# EL-100-020-010-AnalogIN.net
KiCad netlist of a schematic drawn in EAGLE
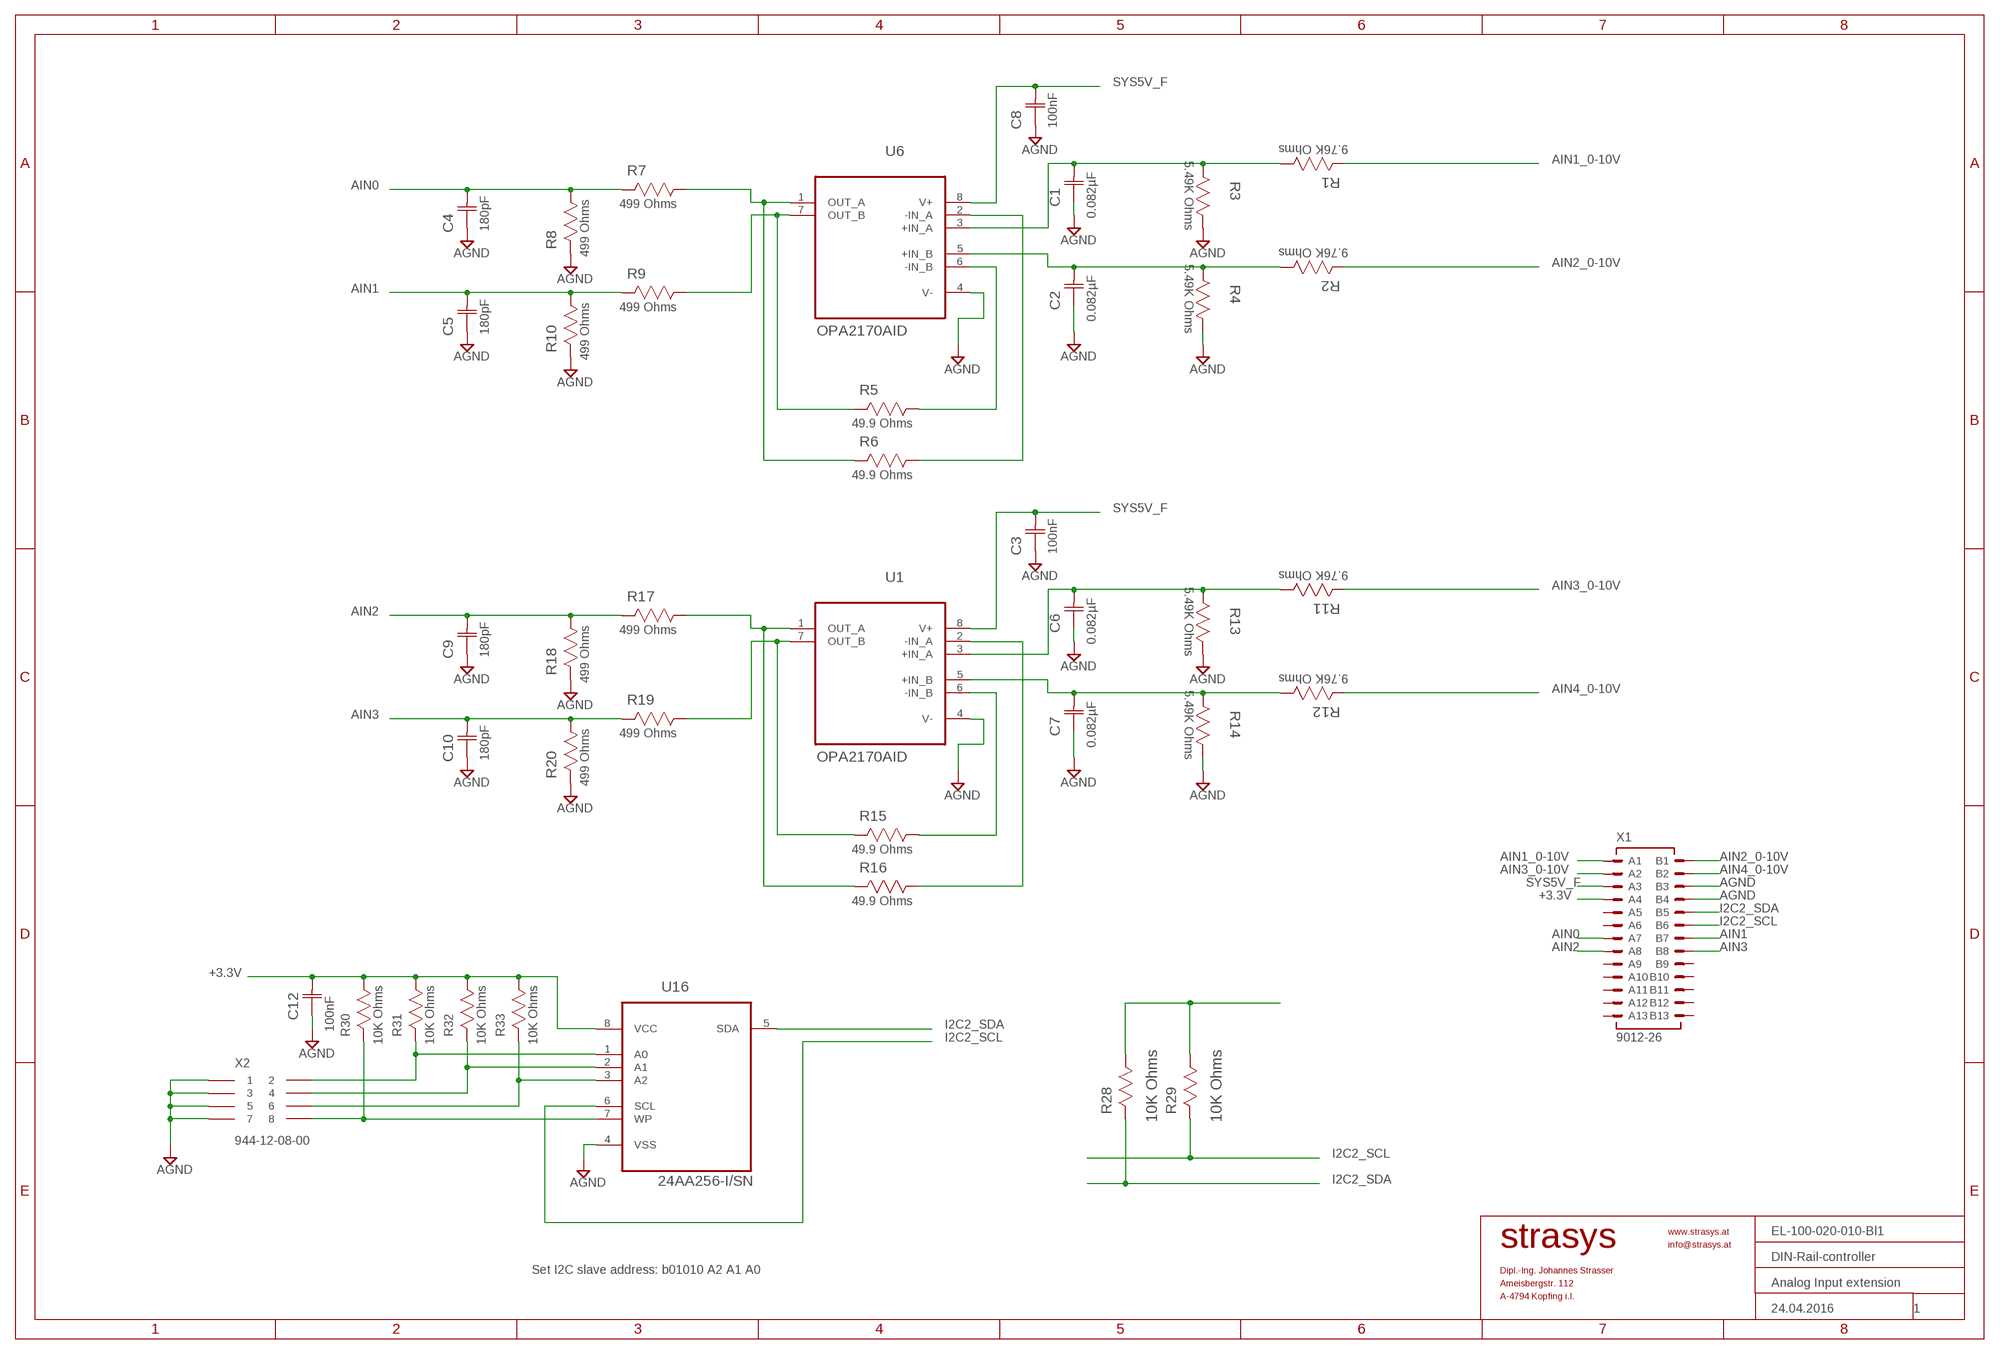
[diagram p0: schematic, sheet 1]

(export (version "E")
  (design (tool "Eeschema 10.0.6"))
  (components
    (comp (ref "C1")
      (value "0.082µF")
      (footprint "eagle-import:CAPC2013X88N")
      (fields
        (field (name "MPN") "C0805C180J5GACTU")
        (field (name "TOLERANCE") "±5%")
        (field (name "MPN_1") "MC0805B823K500CT")
        (field (name "OC_FARNELL") "1759264")
        (field (name "SUPPLIER") "MULTICOMP")
        (field (name "TOLERANCE_1") "±10%")
      )
      (libsource (lib "eagle-import") (part "C0805C180J5GACTU"))
    )
    (comp (ref "C2")
      (value "0.082µF")
      (footprint "eagle-import:CAPC2013X88N")
      (fields
        (field (name "MPN") "C0805C180J5GACTU")
        (field (name "TOLERANCE") "±5%")
        (field (name "MPN_1") "MC0805B823K500CT")
        (field (name "OC_FARNELL") "1759264")
        (field (name "SUPPLIER") "MULTICOMP")
        (field (name "TOLERANCE_1") "±10%")
      )
      (libsource (lib "eagle-import") (part "C0805C180J5GACTU"))
    )
    (comp (ref "C3")
      (value "100nF")
      (footprint "eagle-import:CAPC2013X110N")
      (fields
        (field (name "MPN") "C0805C104K5RACTU")
        (field (name "TOLERANCE") "±10%")
        (field (name "MF") "KEMET")
      )
      (libsource (lib "eagle-import") (part "C0805C104K5RACTU"))
    )
    (comp (ref "C4")
      (value "180pF")
      (footprint "eagle-import:CAPC2013X88N")
      (fields
        (field (name "MPN") "C0805C180J5GACTU")
        (field (name "TOLERANCE") "±5%")
        (field (name "MF") "KEMET")
        (field (name "MPN_1") "C0805C181J5GACTU")
        (field (name "OC_FARNELL") "1414674")
      )
      (libsource (lib "eagle-import") (part "C0805C180J5GACTU"))
    )
    (comp (ref "C5")
      (value "180pF")
      (footprint "eagle-import:CAPC2013X88N")
      (fields
        (field (name "MPN") "C0805C180J5GACTU")
        (field (name "TOLERANCE") "±5%")
        (field (name "MF") "KEMET")
        (field (name "MPN_1") "C0805C181J5GACTU")
        (field (name "OC_FARNELL") "1414674")
      )
      (libsource (lib "eagle-import") (part "C0805C180J5GACTU"))
    )
    (comp (ref "C6")
      (value "0.082µF")
      (footprint "eagle-import:CAPC2013X88N")
      (fields
        (field (name "MPN") "C0805C180J5GACTU")
        (field (name "TOLERANCE") "±5%")
        (field (name "MPN_1") "MC0805B823K500CT")
        (field (name "OC_FARNELL") "1759264")
        (field (name "SUPPLIER") "MULTICOMP")
        (field (name "TOLERANCE_1") "±10%")
      )
      (libsource (lib "eagle-import") (part "C0805C180J5GACTU"))
    )
    (comp (ref "C7")
      (value "0.082µF")
      (footprint "eagle-import:CAPC2013X88N")
      (fields
        (field (name "MPN") "C0805C180J5GACTU")
        (field (name "TOLERANCE") "±5%")
        (field (name "MPN_1") "MC0805B823K500CT")
        (field (name "OC_FARNELL") "1759264")
        (field (name "SUPPLIER") "MULTICOMP")
        (field (name "TOLERANCE_1") "±10%")
      )
      (libsource (lib "eagle-import") (part "C0805C180J5GACTU"))
    )
    (comp (ref "C8")
      (value "100nF")
      (footprint "eagle-import:CAPC2013X110N")
      (fields
        (field (name "MPN") "C0805C104K5RACTU")
        (field (name "TOLERANCE") "±10%")
        (field (name "MF") "KEMET")
      )
      (libsource (lib "eagle-import") (part "C0805C104K5RACTU"))
    )
    (comp (ref "C9")
      (value "180pF")
      (footprint "eagle-import:CAPC2013X88N")
      (fields
        (field (name "MPN") "C0805C180J5GACTU")
        (field (name "TOLERANCE") "±5%")
        (field (name "MF") "KEMET")
        (field (name "MPN_1") "C0805C181J5GACTU")
        (field (name "OC_FARNELL") "1414674")
      )
      (libsource (lib "eagle-import") (part "C0805C180J5GACTU"))
    )
    (comp (ref "C10")
      (value "180pF")
      (footprint "eagle-import:CAPC2013X88N")
      (fields
        (field (name "MPN") "C0805C180J5GACTU")
        (field (name "TOLERANCE") "±5%")
        (field (name "MF") "KEMET")
        (field (name "MPN_1") "C0805C181J5GACTU")
        (field (name "OC_FARNELL") "1414674")
      )
      (libsource (lib "eagle-import") (part "C0805C180J5GACTU"))
    )
    (comp (ref "C12")
      (value "100nF")
      (footprint "eagle-import:CAPC2013X110N")
      (fields
        (field (name "MPN") "C0805C104K5RACTU")
        (field (name "TOLERANCE") "±10%")
        (field (name "MF") "KEMET")
      )
      (libsource (lib "eagle-import") (part "C0805C104K5RACTU"))
    )
    (comp (ref "R1")
      (value "9.76K Ohms")
      (footprint "eagle-import:RESC2013X65N")
      (fields
        (field (name "MPN") "CRCW08059K76FKEA")
        (field (name "TOLERANCE") "±1%")
        (field (name "MPN_1") "MCTC0525B9761T5E")
        (field (name "OC_FARNELL") "1575899 ")
        (field (name "SUPPLIER") "MULTICOMP")
        (field (name "TOLERANCE_1") "±0.1%")
      )
      (libsource (lib "eagle-import") (part "CRCW08059K76FKEA"))
    )
    (comp (ref "R2")
      (value "9.76K Ohms")
      (footprint "eagle-import:RESC2013X65N")
      (fields
        (field (name "MPN") "CRCW08059K76FKEA")
        (field (name "TOLERANCE") "±1%")
        (field (name "MPN_1") "MCTC0525B9761T5E")
        (field (name "OC_FARNELL") "1575899 ")
        (field (name "SUPPLIER") "MULTICOMP")
        (field (name "TOLERANCE_1") "±0.1%")
      )
      (libsource (lib "eagle-import") (part "CRCW08059K76FKEA"))
    )
    (comp (ref "R3")
      (value "5.49K Ohms")
      (footprint "eagle-import:RESC2013X65N")
      (fields
        (field (name "MPN") "CRCW08055K49FKEA")
        (field (name "TOLERANCE") "±1%")
        (field (name "MPN_1") "PCF0805R-5K49BI")
        (field (name "OC_FARNELL") "1160182")
        (field (name "SUPPLIER") "WELWYN")
        (field (name "TOLERANCE_1") "±0.1%")
      )
      (libsource (lib "eagle-import") (part "CRCW08055K49FKEA"))
    )
    (comp (ref "R4")
      (value "5.49K Ohms")
      (footprint "eagle-import:RESC2013X65N")
      (fields
        (field (name "MPN") "CRCW08055K49FKEA")
        (field (name "TOLERANCE") "±1%")
        (field (name "MPN_1") "PCF0805R-5K49BI")
        (field (name "OC_FARNELL") "1160182")
        (field (name "SUPPLIER") "WELWYN")
        (field (name "TOLERANCE_1") "±0.1%")
      )
      (libsource (lib "eagle-import") (part "CRCW08055K49FKEA"))
    )
    (comp (ref "R5")
      (value "49.9 Ohms")
      (footprint "eagle-import:RESC2013X65N")
      (fields
        (field (name "MPN") "CRCW080549R9FKEA")
        (field (name "TOLERANCE") "±1%")
        (field (name "MPN_1") "MCTC0525B499JT5E")
        (field (name "OC_FARNELL") "1575515")
        (field (name "SUPPLIER") "MULTICOMP")
        (field (name "TOLERANCE_1") "±0.1%")
        (field (name "WATTAGE") "0.1 W")
      )
      (libsource (lib "eagle-import") (part "CRCW080549R9FKEA"))
    )
    (comp (ref "R6")
      (value "49.9 Ohms")
      (footprint "eagle-import:RESC2013X65N")
      (fields
        (field (name "MPN") "CRCW080549R9FKEA")
        (field (name "TOLERANCE") "±1%")
        (field (name "MPN_1") "MCTC0525B499JT5E")
        (field (name "OC_FARNELL") "1575515")
        (field (name "SUPPLIER") "MULTICOMP")
        (field (name "TOLERANCE_1") "±0.1%")
        (field (name "WATTAGE") "0.1 W")
      )
      (libsource (lib "eagle-import") (part "CRCW080549R9FKEA"))
    )
    (comp (ref "R7")
      (value "499 Ohms")
      (footprint "eagle-import:RESC2013X65N")
      (fields
        (field (name "MPN") "CRCW0805499RFKEA")
        (field (name "TOLERANCE") "±1%")
        (field (name "MPN_1") "ERA6AEB4990V")
        (field (name "OC_FARNELL") "1810472 ")
        (field (name "SUPPLIER") "PANASONIC ELECTRONIC COMPONENTS")
        (field (name "TOLERANCE_1") "±0.1%")
      )
      (libsource (lib "eagle-import") (part "CRCW0805499RFKEA"))
    )
    (comp (ref "R8")
      (value "499 Ohms")
      (footprint "eagle-import:RESC2013X65N")
      (fields
        (field (name "MPN") "CRCW0805499RFKEA")
        (field (name "TOLERANCE") "±1%")
        (field (name "MPN_1") "ERA6AEB4990V")
        (field (name "OC_FARNELL") "1810472 ")
        (field (name "SUPPLIER") "PANASONIC ELECTRONIC COMPONENTS")
        (field (name "TOLERANCE_1") "±0.1%")
      )
      (libsource (lib "eagle-import") (part "CRCW0805499RFKEA"))
    )
    (comp (ref "R9")
      (value "499 Ohms")
      (footprint "eagle-import:RESC2013X65N")
      (fields
        (field (name "MPN") "CRCW0805499RFKEA")
        (field (name "TOLERANCE") "±1%")
        (field (name "MPN_1") "ERA6AEB4990V")
        (field (name "OC_FARNELL") "1810472 ")
        (field (name "SUPPLIER") "PANASONIC ELECTRONIC COMPONENTS")
        (field (name "TOLERANCE_1") "±0.1%")
      )
      (libsource (lib "eagle-import") (part "CRCW0805499RFKEA"))
    )
    (comp (ref "R10")
      (value "499 Ohms")
      (footprint "eagle-import:RESC2013X65N")
      (fields
        (field (name "MPN") "CRCW0805499RFKEA")
        (field (name "TOLERANCE") "±1%")
        (field (name "MPN_1") "ERA6AEB4990V")
        (field (name "OC_FARNELL") "1810472 ")
        (field (name "SUPPLIER") "PANASONIC ELECTRONIC COMPONENTS")
        (field (name "TOLERANCE_1") "±0.1%")
      )
      (libsource (lib "eagle-import") (part "CRCW0805499RFKEA"))
    )
    (comp (ref "R11")
      (value "9.76K Ohms")
      (footprint "eagle-import:RESC2013X65N")
      (fields
        (field (name "MPN") "CRCW08059K76FKEA")
        (field (name "TOLERANCE") "±1%")
        (field (name "MPN_1") "MCTC0525B9761T5E")
        (field (name "OC_FARNELL") "1575899 ")
        (field (name "SUPPLIER") "MULTICOMP")
        (field (name "TOLERANCE_1") "±0.1%")
      )
      (libsource (lib "eagle-import") (part "CRCW08059K76FKEA"))
    )
    (comp (ref "R12")
      (value "9.76K Ohms")
      (footprint "eagle-import:RESC2013X65N")
      (fields
        (field (name "MPN") "CRCW08059K76FKEA")
        (field (name "TOLERANCE") "±1%")
        (field (name "MPN_1") "MCTC0525B9761T5E")
        (field (name "OC_FARNELL") "1575899 ")
        (field (name "SUPPLIER") "MULTICOMP")
        (field (name "TOLERANCE_1") "±0.1%")
      )
      (libsource (lib "eagle-import") (part "CRCW08059K76FKEA"))
    )
    (comp (ref "R13")
      (value "5.49K Ohms")
      (footprint "eagle-import:RESC2013X65N")
      (fields
        (field (name "MPN") "CRCW08055K49FKEA")
        (field (name "TOLERANCE") "±1%")
        (field (name "MPN_1") "PCF0805R-5K49BI")
        (field (name "OC_FARNELL") "1160182")
        (field (name "SUPPLIER") "WELWYN")
        (field (name "TOLERANCE_1") "±0.1%")
      )
      (libsource (lib "eagle-import") (part "CRCW08055K49FKEA"))
    )
    (comp (ref "R14")
      (value "5.49K Ohms")
      (footprint "eagle-import:RESC2013X65N")
      (fields
        (field (name "MPN") "CRCW08055K49FKEA")
        (field (name "TOLERANCE") "±1%")
        (field (name "MPN_1") "PCF0805R-5K49BI")
        (field (name "OC_FARNELL") "1160182")
        (field (name "SUPPLIER") "WELWYN")
        (field (name "TOLERANCE_1") "±0.1%")
      )
      (libsource (lib "eagle-import") (part "CRCW08055K49FKEA"))
    )
    (comp (ref "R15")
      (value "49.9 Ohms")
      (footprint "eagle-import:RESC2013X65N")
      (fields
        (field (name "MPN") "CRCW080549R9FKEA")
        (field (name "TOLERANCE") "±1%")
        (field (name "MPN_1") "MCTC0525B499JT5E")
        (field (name "OC_FARNELL") "1575515")
        (field (name "SUPPLIER") "MULTICOMP")
        (field (name "TOLERANCE_1") "±0.1%")
        (field (name "WATTAGE") "0.1 W")
      )
      (libsource (lib "eagle-import") (part "CRCW080549R9FKEA"))
    )
    (comp (ref "R16")
      (value "49.9 Ohms")
      (footprint "eagle-import:RESC2013X65N")
      (fields
        (field (name "MPN") "CRCW080549R9FKEA")
        (field (name "TOLERANCE") "±1%")
        (field (name "MPN_1") "MCTC0525B499JT5E")
        (field (name "OC_FARNELL") "1575515")
        (field (name "SUPPLIER") "MULTICOMP")
        (field (name "TOLERANCE_1") "±0.1%")
        (field (name "WATTAGE") "0.1 W")
      )
      (libsource (lib "eagle-import") (part "CRCW080549R9FKEA"))
    )
    (comp (ref "R17")
      (value "499 Ohms")
      (footprint "eagle-import:RESC2013X65N")
      (fields
        (field (name "MPN") "CRCW0805499RFKEA")
        (field (name "TOLERANCE") "±1%")
        (field (name "MPN_1") "ERA6AEB4990V")
        (field (name "OC_FARNELL") "1810472 ")
        (field (name "SUPPLIER") "PANASONIC ELECTRONIC COMPONENTS")
        (field (name "TOLERANCE_1") "±0.1%")
      )
      (libsource (lib "eagle-import") (part "CRCW0805499RFKEA"))
    )
    (comp (ref "R18")
      (value "499 Ohms")
      (footprint "eagle-import:RESC2013X65N")
      (fields
        (field (name "MPN") "CRCW0805499RFKEA")
        (field (name "TOLERANCE") "±1%")
        (field (name "MPN_1") "ERA6AEB4990V")
        (field (name "OC_FARNELL") "1810472 ")
        (field (name "SUPPLIER") "PANASONIC ELECTRONIC COMPONENTS")
        (field (name "TOLERANCE_1") "±0.1%")
      )
      (libsource (lib "eagle-import") (part "CRCW0805499RFKEA"))
    )
    (comp (ref "R19")
      (value "499 Ohms")
      (footprint "eagle-import:RESC2013X65N")
      (fields
        (field (name "MPN") "CRCW0805499RFKEA")
        (field (name "TOLERANCE") "±1%")
        (field (name "MPN_1") "ERA6AEB4990V")
        (field (name "OC_FARNELL") "1810472 ")
        (field (name "SUPPLIER") "PANASONIC ELECTRONIC COMPONENTS")
        (field (name "TOLERANCE_1") "±0.1%")
      )
      (libsource (lib "eagle-import") (part "CRCW0805499RFKEA"))
    )
    (comp (ref "R20")
      (value "499 Ohms")
      (footprint "eagle-import:RESC2013X65N")
      (fields
        (field (name "MPN") "CRCW0805499RFKEA")
        (field (name "TOLERANCE") "±1%")
        (field (name "MPN_1") "ERA6AEB4990V")
        (field (name "OC_FARNELL") "1810472 ")
        (field (name "SUPPLIER") "PANASONIC ELECTRONIC COMPONENTS")
        (field (name "TOLERANCE_1") "±0.1%")
      )
      (libsource (lib "eagle-import") (part "CRCW0805499RFKEA"))
    )
    (comp (ref "R28")
      (value "10K Ohms")
      (footprint "eagle-import:RESC2013X65N")
      (fields
        (field (name "MPN") "CRCW080510K0JNEA")
        (field (name "TOLERANCE") "±5%")
        (field (name "MF") "VISHAY DRALORIC")
      )
      (libsource (lib "eagle-import") (part "CRCW080510K0JNEA"))
    )
    (comp (ref "R29")
      (value "10K Ohms")
      (footprint "eagle-import:RESC2013X65N")
      (fields
        (field (name "MPN") "CRCW080510K0JNEA")
        (field (name "TOLERANCE") "±5%")
        (field (name "MF") "VISHAY DRALORIC")
      )
      (libsource (lib "eagle-import") (part "CRCW080510K0JNEA"))
    )
    (comp (ref "R30")
      (value "10K Ohms")
      (footprint "eagle-import:RESC2013X65N")
      (fields
        (field (name "MPN") "CRCW080510K0JNEA")
        (field (name "TOLERANCE") "±5%")
        (field (name "MF") "VISHAY DRALORIC")
      )
      (libsource (lib "eagle-import") (part "CRCW080510K0JNEA"))
    )
    (comp (ref "R31")
      (value "10K Ohms")
      (footprint "eagle-import:RESC2013X65N")
      (fields
        (field (name "MPN") "CRCW080510K0JNEA")
        (field (name "TOLERANCE") "±5%")
        (field (name "MF") "VISHAY DRALORIC")
      )
      (libsource (lib "eagle-import") (part "CRCW080510K0JNEA"))
    )
    (comp (ref "R32")
      (value "10K Ohms")
      (footprint "eagle-import:RESC2013X65N")
      (fields
        (field (name "MPN") "CRCW080510K0JNEA")
        (field (name "TOLERANCE") "±5%")
        (field (name "MF") "VISHAY DRALORIC")
      )
      (libsource (lib "eagle-import") (part "CRCW080510K0JNEA"))
    )
    (comp (ref "R33")
      (value "10K Ohms")
      (footprint "eagle-import:RESC2013X65N")
      (fields
        (field (name "MPN") "CRCW080510K0JNEA")
        (field (name "TOLERANCE") "±5%")
        (field (name "MF") "VISHAY DRALORIC")
      )
      (libsource (lib "eagle-import") (part "CRCW080510K0JNEA"))
    )
    (comp (ref "U1")
      (value "OPA2170AID")
      (footprint "eagle-import:SOIC127P600X175-8N")
      (fields (field (name "MF") "TEXAS INSTRUMENTS"))
      (libsource (lib "eagle-import") (part "OPA2170AID"))
    )
    (comp (ref "U6")
      (value "OPA2170AID")
      (footprint "eagle-import:SOIC127P600X175-8N")
      (fields (field (name "MF") "TEXAS INSTRUMENTS"))
      (libsource (lib "eagle-import") (part "OPA2170AID"))
    )
    (comp (ref "U16")
      (value "24AA256-I/SN")
      (footprint "eagle-import:SOIC127P600X175-8N")
      (fields (field (name "MF") "MICROCHIP"))
      (libsource (lib "eagle-import") (part "24AA256-I/SN"))
    )
    (comp (ref "X1")
      (value "9012-26")
      (footprint "eagle-import:9012-26")
      (libsource (lib "eagle-import") (part "9012-26"))
    )
    (comp (ref "X2")
      (value "944-12-08-00")
      (footprint "eagle-import:2,54_2X8")
      (libsource (lib "eagle-import") (part "944-12-08-00"))
    )
  )
  (nets
    (net (code "1") (name "/+3.3V") (class "Default")
      (node (ref "C12") (pin "2") (pinfunction "C2_2") (pintype "passive"))
      (node (ref "R28") (pin "1") (pinfunction "1_1") (pintype "passive"))
      (node (ref "R29") (pin "1") (pinfunction "1_1") (pintype "passive"))
      (node (ref "R30") (pin "1") (pinfunction "1_1") (pintype "passive"))
      (node (ref "R31") (pin "1") (pinfunction "1_1") (pintype "passive"))
      (node (ref "R32") (pin "1") (pinfunction "1_1") (pintype "passive"))
      (node (ref "R33") (pin "1") (pinfunction "1_1") (pintype "passive"))
      (node (ref "U16") (pin "8") (pinfunction "VCC_8") (pintype "power_in"))
      (node (ref "X1") (pin "A4") (pinfunction "A4_A4") (pintype "passive"))
    )
    (net (code "2") (name "/AIN0") (class "Default")
      (node (ref "C4") (pin "2") (pinfunction "C2_2") (pintype "passive"))
      (node (ref "R7") (pin "2") (pinfunction "2_2") (pintype "passive"))
      (node (ref "R8") (pin "1") (pinfunction "1_1") (pintype "passive"))
      (node (ref "X1") (pin "A7") (pinfunction "A7_A7") (pintype "passive"))
    )
    (net (code "3") (name "/AIN1") (class "Default")
      (node (ref "C5") (pin "2") (pinfunction "C2_2") (pintype "passive"))
      (node (ref "R10") (pin "1") (pinfunction "1_1") (pintype "passive"))
      (node (ref "R9") (pin "2") (pinfunction "2_2") (pintype "passive"))
      (node (ref "X1") (pin "B7") (pinfunction "B7_B7") (pintype "passive"))
    )
    (net (code "4") (name "/AIN1_0-10V") (class "Default")
      (node (ref "R1") (pin "2") (pinfunction "2_2") (pintype "passive"))
      (node (ref "X1") (pin "A1") (pinfunction "A1_A1") (pintype "passive"))
    )
    (net (code "5") (name "/AIN2") (class "Default")
      (node (ref "C9") (pin "2") (pinfunction "C2_2") (pintype "passive"))
      (node (ref "R17") (pin "2") (pinfunction "2_2") (pintype "passive"))
      (node (ref "R18") (pin "1") (pinfunction "1_1") (pintype "passive"))
      (node (ref "X1") (pin "A8") (pinfunction "A8_A8") (pintype "passive"))
    )
    (net (code "6") (name "/AIN2_0-10V") (class "Default")
      (node (ref "R2") (pin "2") (pinfunction "2_2") (pintype "passive"))
      (node (ref "X1") (pin "B1") (pinfunction "B1_B1") (pintype "passive"))
    )
    (net (code "7") (name "/AIN3") (class "Default")
      (node (ref "C10") (pin "2") (pinfunction "C2_2") (pintype "passive"))
      (node (ref "R19") (pin "2") (pinfunction "2_2") (pintype "passive"))
      (node (ref "R20") (pin "1") (pinfunction "1_1") (pintype "passive"))
      (node (ref "X1") (pin "B8") (pinfunction "B8_B8") (pintype "passive"))
    )
    (net (code "8") (name "/AIN3_0-10V") (class "Default")
      (node (ref "R11") (pin "2") (pinfunction "2_2") (pintype "passive"))
      (node (ref "X1") (pin "A2") (pinfunction "A2_A2") (pintype "passive"))
    )
    (net (code "9") (name "/AIN4_0-10V") (class "Default")
      (node (ref "R12") (pin "2") (pinfunction "2_2") (pintype "passive"))
      (node (ref "X1") (pin "B2") (pinfunction "B2_B2") (pintype "passive"))
    )
    (net (code "10") (name "/I2C2_SCL") (class "Default")
      (node (ref "R29") (pin "2") (pinfunction "2_2") (pintype "passive"))
      (node (ref "U16") (pin "6") (pinfunction "SCL_6") (pintype "input"))
      (node (ref "X1") (pin "B6") (pinfunction "B6_B6") (pintype "passive"))
    )
    (net (code "11") (name "/I2C2_SDA") (class "Default")
      (node (ref "R28") (pin "2") (pinfunction "2_2") (pintype "passive"))
      (node (ref "U16") (pin "5") (pinfunction "SDA_5") (pintype "bidirectional"))
      (node (ref "X1") (pin "B5") (pinfunction "B5_B5") (pintype "passive"))
    )
    (net (code "12") (name "/SYS5V_F") (class "Default")
      (node (ref "C3") (pin "2") (pinfunction "C2_2") (pintype "passive"))
      (node (ref "C8") (pin "2") (pinfunction "C2_2") (pintype "passive"))
      (node (ref "U1") (pin "8") (pinfunction "V+_8") (pintype "power_in"))
      (node (ref "U6") (pin "8") (pinfunction "V+_8") (pintype "power_in"))
      (node (ref "X1") (pin "A3") (pinfunction "A3_A3") (pintype "passive"))
    )
    (net (code "13") (name "AGND") (class "Default")
      (node (ref "C1") (pin "1") (pinfunction "C1_1") (pintype "passive"))
      (node (ref "C10") (pin "1") (pinfunction "C1_1") (pintype "passive"))
      (node (ref "C12") (pin "1") (pinfunction "C1_1") (pintype "passive"))
      (node (ref "C2") (pin "1") (pinfunction "C1_1") (pintype "passive"))
      (node (ref "C3") (pin "1") (pinfunction "C1_1") (pintype "passive"))
      (node (ref "C4") (pin "1") (pinfunction "C1_1") (pintype "passive"))
      (node (ref "C5") (pin "1") (pinfunction "C1_1") (pintype "passive"))
      (node (ref "C6") (pin "1") (pinfunction "C1_1") (pintype "passive"))
      (node (ref "C7") (pin "1") (pinfunction "C1_1") (pintype "passive"))
      (node (ref "C8") (pin "1") (pinfunction "C1_1") (pintype "passive"))
      (node (ref "C9") (pin "1") (pinfunction "C1_1") (pintype "passive"))
      (node (ref "R10") (pin "2") (pinfunction "2_2") (pintype "passive"))
      (node (ref "R13") (pin "1") (pinfunction "1_1") (pintype "passive"))
      (node (ref "R14") (pin "1") (pinfunction "1_1") (pintype "passive"))
      (node (ref "R18") (pin "2") (pinfunction "2_2") (pintype "passive"))
      (node (ref "R20") (pin "2") (pinfunction "2_2") (pintype "passive"))
      (node (ref "R3") (pin "1") (pinfunction "1_1") (pintype "passive"))
      (node (ref "R4") (pin "1") (pinfunction "1_1") (pintype "passive"))
      (node (ref "R8") (pin "2") (pinfunction "2_2") (pintype "passive"))
      (node (ref "U1") (pin "4") (pinfunction "V-_4") (pintype "passive"))
      (node (ref "U16") (pin "4") (pinfunction "VSS_4") (pintype "passive"))
      (node (ref "U6") (pin "4") (pinfunction "V-_4") (pintype "passive"))
      (node (ref "X1") (pin "B3") (pinfunction "B3_B3") (pintype "passive"))
      (node (ref "X1") (pin "B4") (pinfunction "B4_B4") (pintype "passive"))
      (node (ref "X2") (pin "P1") (pinfunction "1_P1") (pintype "bidirectional"))
      (node (ref "X2") (pin "P3") (pinfunction "3_P3") (pintype "bidirectional"))
      (node (ref "X2") (pin "P5") (pinfunction "5_P5") (pintype "bidirectional"))
      (node (ref "X2") (pin "P7") (pinfunction "7_P7") (pintype "bidirectional"))
    )
    (net (code "14") (name "Net-(C1-C2)") (class "Default")
      (node (ref "C1") (pin "2") (pinfunction "C2_2") (pintype "passive"))
      (node (ref "R1") (pin "1") (pinfunction "1_1") (pintype "passive"))
      (node (ref "R3") (pin "2") (pinfunction "2_2") (pintype "passive"))
      (node (ref "U6") (pin "3") (pinfunction "+IN_A_3") (pintype "input"))
    )
    (net (code "15") (name "Net-(C2-C2)") (class "Default")
      (node (ref "C2") (pin "2") (pinfunction "C2_2") (pintype "passive"))
      (node (ref "R2") (pin "1") (pinfunction "1_1") (pintype "passive"))
      (node (ref "R4") (pin "2") (pinfunction "2_2") (pintype "passive"))
      (node (ref "U6") (pin "5") (pinfunction "+IN_B_5") (pintype "input"))
    )
    (net (code "16") (name "Net-(C6-C2)") (class "Default")
      (node (ref "C6") (pin "2") (pinfunction "C2_2") (pintype "passive"))
      (node (ref "R11") (pin "1") (pinfunction "1_1") (pintype "passive"))
      (node (ref "R13") (pin "2") (pinfunction "2_2") (pintype "passive"))
      (node (ref "U1") (pin "3") (pinfunction "+IN_A_3") (pintype "input"))
    )
    (net (code "17") (name "Net-(C7-C2)") (class "Default")
      (node (ref "C7") (pin "2") (pinfunction "C2_2") (pintype "passive"))
      (node (ref "R12") (pin "1") (pinfunction "1_1") (pintype "passive"))
      (node (ref "R14") (pin "2") (pinfunction "2_2") (pintype "passive"))
      (node (ref "U1") (pin "5") (pinfunction "+IN_B_5") (pintype "input"))
    )
    (net (code "18") (name "Net-(U1--IN_A)") (class "Default")
      (node (ref "R16") (pin "1") (pinfunction "1_1") (pintype "passive"))
      (node (ref "U1") (pin "2") (pinfunction "-IN_A_2") (pintype "input"))
    )
    (net (code "19") (name "Net-(U1--IN_B)") (class "Default")
      (node (ref "R15") (pin "1") (pinfunction "1_1") (pintype "passive"))
      (node (ref "U1") (pin "6") (pinfunction "-IN_B_6") (pintype "input"))
    )
    (net (code "20") (name "Net-(U1-OUT_A)") (class "Default")
      (node (ref "R16") (pin "2") (pinfunction "2_2") (pintype "passive"))
      (node (ref "R17") (pin "1") (pinfunction "1_1") (pintype "passive"))
      (node (ref "U1") (pin "1") (pinfunction "OUT_A_1") (pintype "output"))
    )
    (net (code "21") (name "Net-(U1-OUT_B)") (class "Default")
      (node (ref "R15") (pin "2") (pinfunction "2_2") (pintype "passive"))
      (node (ref "R19") (pin "1") (pinfunction "1_1") (pintype "passive"))
      (node (ref "U1") (pin "7") (pinfunction "OUT_B_7") (pintype "output"))
    )
    (net (code "22") (name "Net-(U6--IN_A)") (class "Default")
      (node (ref "R6") (pin "1") (pinfunction "1_1") (pintype "passive"))
      (node (ref "U6") (pin "2") (pinfunction "-IN_A_2") (pintype "input"))
    )
    (net (code "23") (name "Net-(U6--IN_B)") (class "Default")
      (node (ref "R5") (pin "1") (pinfunction "1_1") (pintype "passive"))
      (node (ref "U6") (pin "6") (pinfunction "-IN_B_6") (pintype "input"))
    )
    (net (code "24") (name "Net-(U6-OUT_A)") (class "Default")
      (node (ref "R6") (pin "2") (pinfunction "2_2") (pintype "passive"))
      (node (ref "R7") (pin "1") (pinfunction "1_1") (pintype "passive"))
      (node (ref "U6") (pin "1") (pinfunction "OUT_A_1") (pintype "output"))
    )
    (net (code "25") (name "Net-(U6-OUT_B)") (class "Default")
      (node (ref "R5") (pin "2") (pinfunction "2_2") (pintype "passive"))
      (node (ref "R9") (pin "1") (pinfunction "1_1") (pintype "passive"))
      (node (ref "U6") (pin "7") (pinfunction "OUT_B_7") (pintype "output"))
    )
    (net (code "26") (name "Net-(U16-A0)") (class "Default")
      (node (ref "R31") (pin "2") (pinfunction "2_2") (pintype "passive"))
      (node (ref "U16") (pin "1") (pinfunction "A0_1") (pintype "input"))
      (node (ref "X2") (pin "P2") (pinfunction "2_P2") (pintype "bidirectional"))
    )
    (net (code "27") (name "Net-(U16-A1)") (class "Default")
      (node (ref "R32") (pin "2") (pinfunction "2_2") (pintype "passive"))
      (node (ref "U16") (pin "2") (pinfunction "A1_2") (pintype "input"))
      (node (ref "X2") (pin "P4") (pinfunction "4_P4") (pintype "bidirectional"))
    )
    (net (code "28") (name "Net-(U16-A2)") (class "Default")
      (node (ref "R33") (pin "2") (pinfunction "2_2") (pintype "passive"))
      (node (ref "U16") (pin "3") (pinfunction "A2_3") (pintype "input"))
      (node (ref "X2") (pin "P6") (pinfunction "6_P6") (pintype "bidirectional"))
    )
    (net (code "29") (name "Net-(U16-WP)") (class "Default")
      (node (ref "R30") (pin "2") (pinfunction "2_2") (pintype "passive"))
      (node (ref "U16") (pin "7") (pinfunction "WP_7") (pintype "input"))
      (node (ref "X2") (pin "P8") (pinfunction "8_P8") (pintype "bidirectional"))
    )
    (net (code "30") (name "unconnected-(X1-PadA5)") (class "Default")
      (node (ref "X1") (pin "A5") (pinfunction "A5_A5") (pintype "passive"))
    )
    (net (code "31") (name "unconnected-(X1-PadA6)") (class "Default")
      (node (ref "X1") (pin "A6") (pinfunction "A6_A6") (pintype "passive"))
    )
    (net (code "32") (name "unconnected-(X1-PadA9)") (class "Default")
      (node (ref "X1") (pin "A9") (pinfunction "A9_A9") (pintype "passive"))
    )
    (net (code "33") (name "unconnected-(X1-PadA10)") (class "Default")
      (node (ref "X1") (pin "A10") (pinfunction "A10_A10") (pintype "passive"))
    )
    (net (code "34") (name "unconnected-(X1-PadA11)") (class "Default")
      (node (ref "X1") (pin "A11") (pinfunction "A11_A11") (pintype "passive"))
    )
    (net (code "35") (name "unconnected-(X1-PadA12)") (class "Default")
      (node (ref "X1") (pin "A12") (pinfunction "A12_A12") (pintype "passive"))
    )
    (net (code "36") (name "unconnected-(X1-PadA13)") (class "Default")
      (node (ref "X1") (pin "A13") (pinfunction "A13_A13") (pintype "passive"))
    )
    (net (code "37") (name "unconnected-(X1-PadB9)") (class "Default")
      (node (ref "X1") (pin "B9") (pinfunction "B9_B9") (pintype "passive"))
    )
    (net (code "38") (name "unconnected-(X1-PadB10)") (class "Default")
      (node (ref "X1") (pin "B10") (pinfunction "B10_B10") (pintype "passive"))
    )
    (net (code "39") (name "unconnected-(X1-PadB11)") (class "Default")
      (node (ref "X1") (pin "B11") (pinfunction "B11_B11") (pintype "passive"))
    )
    (net (code "40") (name "unconnected-(X1-PadB12)") (class "Default")
      (node (ref "X1") (pin "B12") (pinfunction "B12_B12") (pintype "passive"))
    )
    (net (code "41") (name "unconnected-(X1-PadB13)") (class "Default")
      (node (ref "X1") (pin "B13") (pinfunction "B13_B13") (pintype "passive"))
    )
  )
)
